# Sound_JQ6500_4.net
KiCad netlist of a schematic drawn in EAGLE
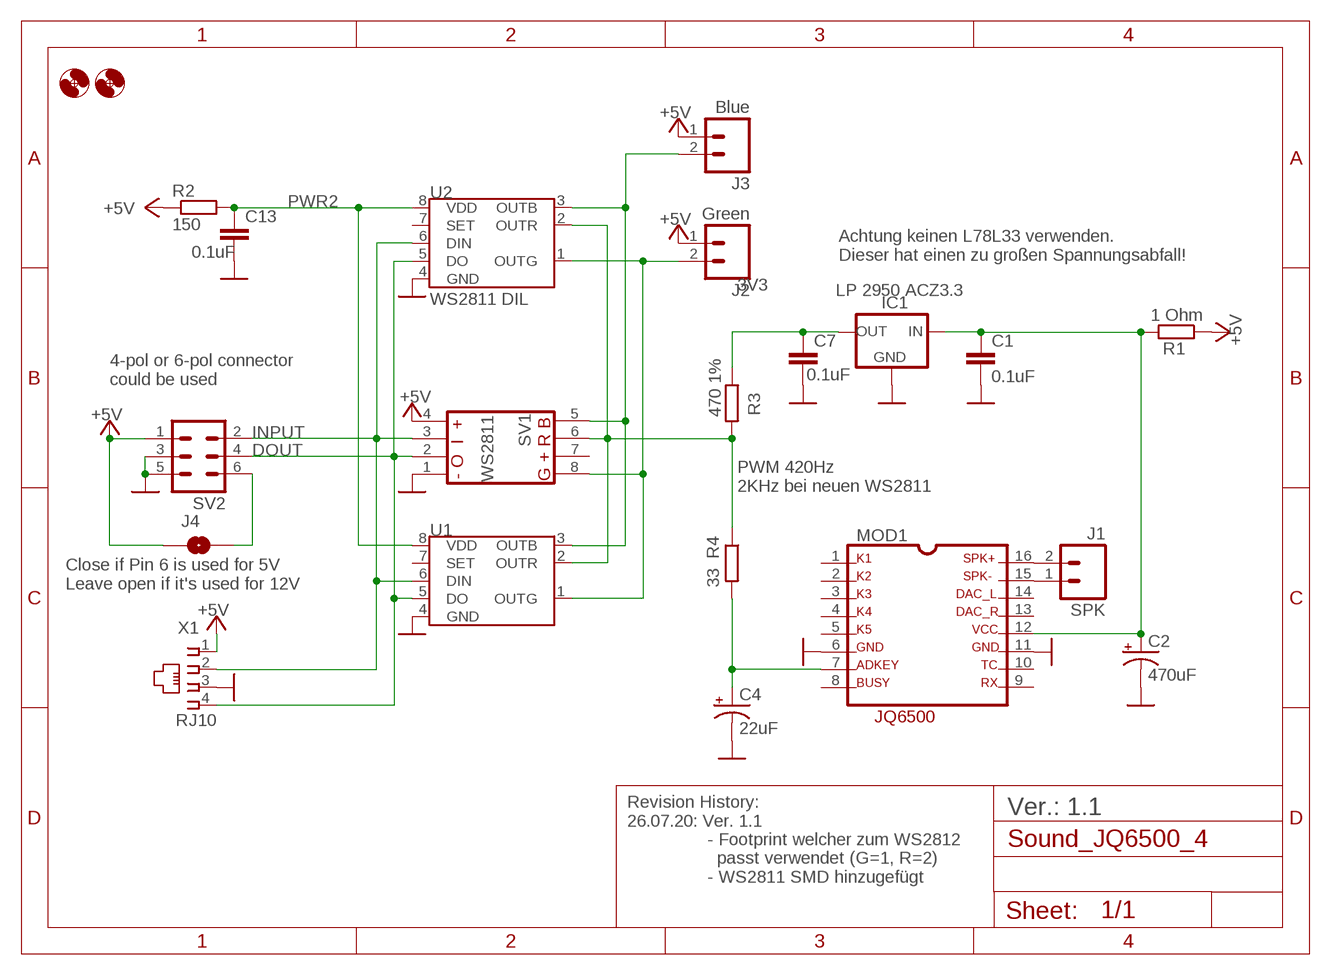
[diagram p0: schematic, sheet 1]

(export (version "E")
  (design (tool "Eeschema 10.0.6"))
  (components
    (comp (ref "C1")
      (value "0.1uF")
      (footprint "eagle-import:CAP-PTH-SMALL-KIT")
      (libsource (lib "eagle-import") (part "0.1UF-50V-20%(PTH)KIT-EZ"))
    )
    (comp (ref "C2")
      (value "470uF")
      (footprint "eagle-import:SPARKFUN-CAPACITORS_CPOL-RADIAL-100UF-25V")
      (libsource (lib "eagle-import") (part "SPARKFUN-CAPACITORS_100UF-25V-20%(PTH)"))
    )
    (comp (ref "C4")
      (value "22uF")
      (footprint "eagle-import:CAPACITOR_CPOL-RADIAL-22UF")
      (libsource (lib "eagle-import") (part "CAPACITORS_22UF"))
    )
    (comp (ref "C7")
      (value "0.1uF")
      (footprint "eagle-import:CAP-PTH-SMALL-KIT")
      (libsource (lib "eagle-import") (part "0.1UF-50V-20%(PTH)KIT-EZ"))
    )
    (comp (ref "C13")
      (value "0.1uF")
      (footprint "eagle-import:CAP-PTH-SMALL-KIT")
      (libsource (lib "eagle-import") (part "0.1UF-50V-20%(PTH)KIT-EZ"))
    )
    (comp (ref "H1")
      (value "MOUNT-HOLE3.0")
      (footprint "eagle-import:3,0")
      (libsource (lib "eagle-import") (part "MOUNT-HOLE3.0"))
    )
    (comp (ref "H3")
      (value "MOUNT-HOLE3.0")
      (footprint "eagle-import:3,0")
      (libsource (lib "eagle-import") (part "MOUNT-HOLE3.0"))
    )
    (comp (ref "IC1")
      (value "LP 2950 ACZ3.3")
      (footprint "eagle-import:78LXX")
      (libsource (lib "eagle-import") (part "78LXX"))
    )
    (comp (ref "J1")
      (value "SPK")
      (footprint "eagle-import:1X02")
      (libsource (lib "eagle-import") (part "M02PTH"))
    )
    (comp (ref "J2")
      (value "Green")
      (footprint "eagle-import:1X02")
      (libsource (lib "eagle-import") (part "M02PTH"))
    )
    (comp (ref "J3")
      (value "Blue")
      (footprint "eagle-import:1X02")
      (libsource (lib "eagle-import") (part "M02PTH"))
    )
    (comp (ref "J4")
      (value "SOLDERJUMPERNO")
      (footprint "eagle-import:SJ_2S-NO")
      (libsource (lib "eagle-import") (part "SOLDERJUMPERNO"))
    )
    (comp (ref "MOD1")
      (value "JQ6500")
      (footprint "eagle-import:JQ6500")
      (libsource (lib "eagle-import") (part "JQ6500"))
    )
    (comp (ref "R1")
      (value "1 Ohm")
      (footprint "eagle-import:RCL_0204_5")
      (libsource (lib "eagle-import") (part "RCL_R-EU_0204/5"))
    )
    (comp (ref "R2")
      (value "150")
      (footprint "eagle-import:RCL_0204_5")
      (libsource (lib "eagle-import") (part "RCL_R-EU_0204/5"))
    )
    (comp (ref "R3")
      (value "470 1%")
      (footprint "eagle-import:RCL_0204_5")
      (libsource (lib "eagle-import") (part "RCL_R-EU_0204/5"))
    )
    (comp (ref "R4")
      (value "33")
      (footprint "eagle-import:RCL_0204_5")
      (libsource (lib "eagle-import") (part "RCL_R-EU_0204/5"))
    )
    (comp (ref "SV1")
      (value "S3PO_MODUL_WS2811_SOUND_MP3-TF-16P_WS2811_AND_ATTINY_PUSHBUTTONACTION_4017_2_WS28115V")
      (footprint "eagle-import:S3PO_MODUL_WS2811_SOUND_MP3-TF-16P_WS2811_AND_ATTINY_PUSHBUTTONACTION_4017_2_WS2811_WS2811_5V")
      (libsource (lib "eagle-import") (part "S3PO_MODUL_WS2811_SOUND_MP3-TF-16P_WS2811_AND_ATTINY_PUSHBUTTONACTION_4017_2_WS28115V"))
    )
    (comp (ref "SV2")
      (value "ML6")
      (footprint "eagle-import:ML6")
      (libsource (lib "eagle-import") (part "ML6"))
    )
    (comp (ref "U1")
      (value "WS2811 DIL")
      (footprint "eagle-import:SOP8")
      (libsource (lib "eagle-import") (part "S3PO_MODUL_WS2811_SOUND_MP3-TF-16P_WS2811_AND_ATTINY_WS2811-ICSOP8"))
    )
    (comp (ref "U2")
      (value "WS2811 DIL")
      (footprint "eagle-import:S3PO_MODUL_WS2811_SOUND_MP3-TF-16P_WS2811_AND_ATTINY_WS2811_DIP08")
      (libsource (lib "eagle-import") (part "S3PO_MODUL_WS2811_SOUND_MP3-TF-16P_WS2811_AND_ATTINY_WS2811-ICTINY45-20-DIP"))
    )
    (comp (ref "X1")
      (value "RJ10")
      (footprint "eagle-import:RJ10")
      (libsource (lib "eagle-import") (part "RJ10"))
    )
  )
  (nets
    (net (code "1") (name "+5V") (class "Default")
      (node (ref "J2") (pin "1") (pinfunction "1_1") (pintype "passive"))
      (node (ref "J3") (pin "1") (pinfunction "1_1") (pintype "passive"))
      (node (ref "J4") (pin "1") (pinfunction "1_1") (pintype "passive"))
      (node (ref "R1") (pin "1") (pinfunction "1_1") (pintype "passive"))
      (node (ref "R2") (pin "1") (pinfunction "1_1") (pintype "passive"))
      (node (ref "SV1") (pin "4") (pinfunction "GND_4") (pintype "passive"))
      (node (ref "SV2") (pin "1") (pinfunction "1_1") (pintype "passive"))
      (node (ref "X1") (pin "1") (pinfunction "1_1") (pintype "passive"))
    )
    (net (code "2") (name "/3V3") (class "Default")
      (node (ref "C7") (pin "1") (pinfunction "1_1") (pintype "passive"))
      (node (ref "IC1") (pin "OUT") (pinfunction "OUT_OUT") (pintype "passive"))
      (node (ref "R3") (pin "1") (pinfunction "1_1") (pintype "passive"))
    )
    (net (code "3") (name "/DOUT") (class "Default")
      (node (ref "SV1") (pin "2") (pinfunction "DIN_2") (pintype "passive"))
      (node (ref "SV2") (pin "4") (pinfunction "4_4") (pintype "passive"))
      (node (ref "U1") (pin "5") (pinfunction "DO_5") (pintype "output"))
      (node (ref "U2") (pin "5") (pinfunction "DO_5") (pintype "output"))
      (node (ref "X1") (pin "4") (pinfunction "4_4") (pintype "passive"))
    )
    (net (code "4") (name "/INPUT") (class "Default")
      (node (ref "SV1") (pin "3") (pinfunction "DO_3") (pintype "passive"))
      (node (ref "SV2") (pin "2") (pinfunction "2_2") (pintype "passive"))
      (node (ref "U1") (pin "6") (pinfunction "DIN_6") (pintype "input"))
      (node (ref "U2") (pin "6") (pinfunction "DIN_6") (pintype "input"))
      (node (ref "X1") (pin "2") (pinfunction "2_2") (pintype "passive"))
    )
    (net (code "5") (name "/PWR2") (class "Default")
      (node (ref "C13") (pin "1") (pinfunction "1_1") (pintype "passive"))
      (node (ref "R2") (pin "2") (pinfunction "2_2") (pintype "passive"))
      (node (ref "U1") (pin "8") (pinfunction "VDD_8") (pintype "power_in"))
      (node (ref "U2") (pin "8") (pinfunction "VDD_8") (pintype "power_in"))
    )
    (net (code "6") (name "GND") (class "Default")
      (node (ref "C1") (pin "2") (pinfunction "2_2") (pintype "passive"))
      (node (ref "C13") (pin "2") (pinfunction "2_2") (pintype "passive"))
      (node (ref "C2") (pin "2") (pinfunction "-_2") (pintype "passive"))
      (node (ref "C4") (pin "2") (pinfunction "-_2") (pintype "passive"))
      (node (ref "C7") (pin "2") (pinfunction "2_2") (pintype "passive"))
      (node (ref "IC1") (pin "GND") (pinfunction "GND_GND") (pintype "input"))
      (node (ref "MOD1") (pin "11") (pinfunction "11_11") (pintype "passive"))
      (node (ref "MOD1") (pin "6") (pinfunction "6_6") (pintype "passive"))
      (node (ref "SV1") (pin "1") (pinfunction "VDD_1") (pintype "passive"))
      (node (ref "SV2") (pin "3") (pinfunction "3_3") (pintype "passive"))
      (node (ref "SV2") (pin "5") (pinfunction "5_5") (pintype "passive"))
      (node (ref "U1") (pin "4") (pinfunction "GND_4") (pintype "power_in"))
      (node (ref "U2") (pin "4") (pinfunction "GND_4") (pintype "power_in"))
      (node (ref "X1") (pin "3") (pinfunction "3_3") (pintype "passive"))
    )
    (net (code "7") (name "Net-(C2-+)") (class "Default")
      (node (ref "C1") (pin "1") (pinfunction "1_1") (pintype "passive"))
      (node (ref "C2") (pin "1") (pinfunction "+_1") (pintype "passive"))
      (node (ref "IC1") (pin "IN") (pinfunction "IN_IN") (pintype "input"))
      (node (ref "MOD1") (pin "12") (pinfunction "12_12") (pintype "passive"))
      (node (ref "R1") (pin "2") (pinfunction "2_2") (pintype "passive"))
    )
    (net (code "8") (name "Net-(C4-+)") (class "Default")
      (node (ref "C4") (pin "1") (pinfunction "+_1") (pintype "passive"))
      (node (ref "MOD1") (pin "7") (pinfunction "7_7") (pintype "passive"))
      (node (ref "R4") (pin "2") (pinfunction "2_2") (pintype "passive"))
    )
    (net (code "9") (name "Net-(J1-Pad1)") (class "Default")
      (node (ref "J1") (pin "1") (pinfunction "1_1") (pintype "passive"))
      (node (ref "MOD1") (pin "15") (pinfunction "15_15") (pintype "passive"))
    )
    (net (code "10") (name "Net-(J1-Pad2)") (class "Default")
      (node (ref "J1") (pin "2") (pinfunction "2_2") (pintype "passive"))
      (node (ref "MOD1") (pin "16") (pinfunction "16_16") (pintype "passive"))
    )
    (net (code "11") (name "Net-(J4-Pad2)") (class "Default")
      (node (ref "J4") (pin "2") (pinfunction "2_2") (pintype "passive"))
      (node (ref "SV2") (pin "6") (pinfunction "6_6") (pintype "passive"))
    )
    (net (code "12") (name "Net-(SV1-OUT+)") (class "Default")
      (node (ref "R3") (pin "2") (pinfunction "2_2") (pintype "passive"))
      (node (ref "R4") (pin "1") (pinfunction "1_1") (pintype "passive"))
      (node (ref "SV1") (pin "6") (pinfunction "OUT+_6") (pintype "passive"))
      (node (ref "U1") (pin "2") (pinfunction "OUTR_2") (pintype "open_collector"))
      (node (ref "U2") (pin "2") (pinfunction "OUTR_2") (pintype "open_collector"))
    )
    (net (code "13") (name "Net-(SV1-OUTB)") (class "Default")
      (node (ref "J2") (pin "2") (pinfunction "2_2") (pintype "passive"))
      (node (ref "SV1") (pin "8") (pinfunction "OUTB_8") (pintype "passive"))
      (node (ref "U1") (pin "1") (pinfunction "OUTG_1") (pintype "open_collector"))
      (node (ref "U2") (pin "1") (pinfunction "OUTG_1") (pintype "open_collector"))
    )
    (net (code "14") (name "Net-(SV1-OUTG)") (class "Default")
      (node (ref "J3") (pin "2") (pinfunction "2_2") (pintype "passive"))
      (node (ref "SV1") (pin "5") (pinfunction "OUTG_5") (pintype "passive"))
      (node (ref "U1") (pin "3") (pinfunction "OUTB_3") (pintype "open_collector"))
      (node (ref "U2") (pin "3") (pinfunction "OUTB_3") (pintype "open_collector"))
    )
    (net (code "15") (name "unconnected-(MOD1-Pad1)") (class "Default")
      (node (ref "MOD1") (pin "1") (pinfunction "1_1") (pintype "passive"))
    )
    (net (code "16") (name "unconnected-(MOD1-Pad2)") (class "Default")
      (node (ref "MOD1") (pin "2") (pinfunction "2_2") (pintype "passive"))
    )
    (net (code "17") (name "unconnected-(MOD1-Pad3)") (class "Default")
      (node (ref "MOD1") (pin "3") (pinfunction "3_3") (pintype "passive"))
    )
    (net (code "18") (name "unconnected-(MOD1-Pad4)") (class "Default")
      (node (ref "MOD1") (pin "4") (pinfunction "4_4") (pintype "passive"))
    )
    (net (code "19") (name "unconnected-(MOD1-Pad5)") (class "Default")
      (node (ref "MOD1") (pin "5") (pinfunction "5_5") (pintype "passive"))
    )
    (net (code "20") (name "unconnected-(MOD1-Pad8)") (class "Default")
      (node (ref "MOD1") (pin "8") (pinfunction "8_8") (pintype "passive"))
    )
    (net (code "21") (name "unconnected-(MOD1-Pad9)") (class "Default")
      (node (ref "MOD1") (pin "9") (pinfunction "9_9") (pintype "passive"))
    )
    (net (code "22") (name "unconnected-(MOD1-Pad10)") (class "Default")
      (node (ref "MOD1") (pin "10") (pinfunction "10_10") (pintype "passive"))
    )
    (net (code "23") (name "unconnected-(MOD1-Pad13)") (class "Default")
      (node (ref "MOD1") (pin "13") (pinfunction "13_13") (pintype "passive"))
    )
    (net (code "24") (name "unconnected-(MOD1-Pad14)") (class "Default")
      (node (ref "MOD1") (pin "14") (pinfunction "14_14") (pintype "passive"))
    )
    (net (code "25") (name "unconnected-(SV1-OUTR-Pad7)") (class "Default")
      (node (ref "SV1") (pin "7") (pinfunction "OUTR_7") (pintype "passive"))
    )
    (net (code "26") (name "unconnected-(U1-SET-Pad7)") (class "Default")
      (node (ref "U1") (pin "7") (pinfunction "SET_7") (pintype "bidirectional"))
    )
    (net (code "27") (name "unconnected-(U2-SET-Pad7)") (class "Default")
      (node (ref "U2") (pin "7") (pinfunction "SET_7") (pintype "bidirectional"))
    )
  )
)
